# VDMEDA_Display1.net
KiCad netlist of a schematic drawn in Altium Designer
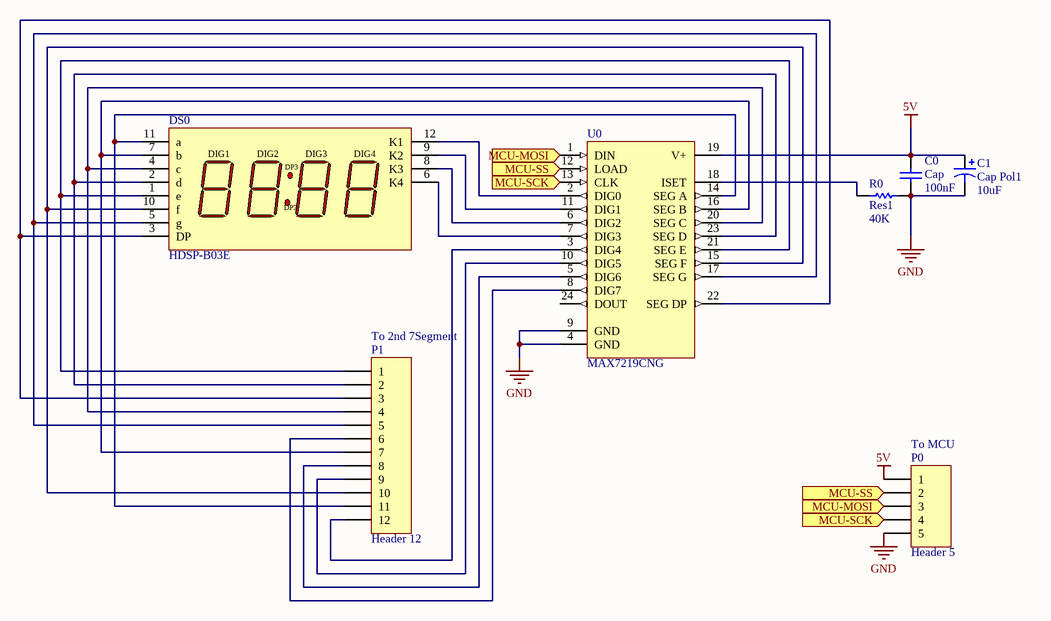
[diagram p0: VDMEDA_Display1.SchDoc]

(export (version "E")
  (design (tool "Eeschema 10.0.6"))
  (components
    (comp (ref "C0")
      (value "Cap")
      (footprint "RAD-0.3")
      (description "Capacitor")
      (fields (field (name "ALTIUM_VALUE") "100nF") (field (name "PUBLISHER") "Altium Limited"))
      (libsource (lib "Miscellaneous Devices") (part "Cap"))
    )
    (comp (ref "C1")
      (value "Cap Pol1")
      (footprint "RB7.6-15")
      (description "Polarized Capacitor (Radial)")
      (fields (field (name "ALTIUM_VALUE") "10uF") (field (name "PUBLISHER") "Altium Limited"))
      (libsource (lib "Miscellaneous Devices") (part "Cap Pol1"))
    )
    (comp (ref "DS0")
      (value "HDSP-B03E")
      (footprint "B-88")
      (description "14.22 mm GaP HER, Untinted, 88:88 4-Digit 7-Segment Display: CC, Gray Surface")
      (fields (field (name "PUBLISHER") "Altium Limited"))
      (libsource (lib "Agilent LED Display 7-Segment, 4-Digit") (part "HDSP-B03E"))
    )
    (comp (ref "P0")
      (value "Header 5")
      (footprint "HDR1X5")
      (description "Header, 5-Pin")
      (fields (field (name "PUBLISHER") "Altium Limited"))
      (libsource (lib "Miscellaneous Connectors") (part "Header 5"))
    )
    (comp (ref "P1")
      (value "Header 12")
      (footprint "HDR1X12")
      (description "Header, 12-Pin")
      (fields (field (name "PUBLISHER") "Altium Limited"))
      (libsource (lib "Miscellaneous Connectors") (part "Header 12"))
    )
    (comp (ref "R0")
      (value "Res1")
      (footprint "AXIAL-0.3")
      (description "Resistor")
      (fields (field (name "ALTIUM_VALUE") "40K") (field (name "PUBLISHER") "Altium Limited"))
      (libsource (lib "Miscellaneous Devices") (part "Res1"))
    )
    (comp (ref "U0")
      (value "MAX7219CNG")
      (footprint "NG24A")
      (description "Serially Interfaced, 8-Digit LED Display Driver")
      (fields (field (name "PUBLISHER") "Altium Limited"))
      (libsource (lib "Maxim Interface Display Driver") (part "MAX7219CNG"))
    )
  )
  (nets
    (net (code "1") (name "/MCU-MOSI") (class "Default")
      (node (ref "P0") (pin "3") (pinfunction "3_3") (pintype "passive"))
      (node (ref "U0") (pin "1") (pinfunction "DIN_1") (pintype "input"))
    )
    (net (code "2") (name "/MCU-SCK") (class "Default")
      (node (ref "P0") (pin "4") (pinfunction "4_4") (pintype "passive"))
      (node (ref "U0") (pin "13") (pinfunction "CLK_13") (pintype "input"))
    )
    (net (code "3") (name "/MCU-SS") (class "Default")
      (node (ref "P0") (pin "2") (pinfunction "2_2") (pintype "passive"))
      (node (ref "U0") (pin "12") (pinfunction "LOAD_12") (pintype "input"))
    )
    (net (code "4") (name "5V") (class "Default")
      (node (ref "C0") (pin "2") (pinfunction "2_2") (pintype "passive"))
      (node (ref "C1") (pin "1") (pinfunction "1_1") (pintype "passive"))
      (node (ref "P0") (pin "1") (pinfunction "1_1") (pintype "passive"))
      (node (ref "U0") (pin "19") (pinfunction "V+_19") (pintype "power_in"))
    )
    (net (code "5") (name "GND") (class "Default")
      (node (ref "C0") (pin "1") (pinfunction "1_1") (pintype "passive"))
      (node (ref "C1") (pin "2") (pinfunction "2_2") (pintype "passive"))
      (node (ref "P0") (pin "5") (pinfunction "5_5") (pintype "passive"))
      (node (ref "R0") (pin "2") (pinfunction "2_2") (pintype "passive"))
      (node (ref "U0") (pin "4") (pinfunction "GND_4") (pintype "power_in"))
      (node (ref "U0") (pin "9") (pinfunction "GND_9") (pintype "power_in"))
    )
    (net (code "6") (name "Net-(DS0-DP)") (class "Default")
      (node (ref "DS0") (pin "3") (pinfunction "DP_3") (pintype "passive"))
      (node (ref "P1") (pin "3") (pinfunction "3_3") (pintype "passive"))
      (node (ref "U0") (pin "22") (pinfunction "SEG_DP_22") (pintype "output"))
    )
    (net (code "7") (name "Net-(DS0-K1)") (class "Default")
      (node (ref "DS0") (pin "12") (pinfunction "K1_12") (pintype "passive"))
      (node (ref "U0") (pin "2") (pinfunction "DIG0_2") (pintype "output"))
    )
    (net (code "8") (name "Net-(DS0-K2)") (class "Default")
      (node (ref "DS0") (pin "9") (pinfunction "K2_9") (pintype "passive"))
      (node (ref "U0") (pin "11") (pinfunction "DIG1_11") (pintype "output"))
    )
    (net (code "9") (name "Net-(DS0-K3)") (class "Default")
      (node (ref "DS0") (pin "8") (pinfunction "K3_8") (pintype "passive"))
      (node (ref "U0") (pin "6") (pinfunction "DIG2_6") (pintype "output"))
    )
    (net (code "10") (name "Net-(DS0-K4)") (class "Default")
      (node (ref "DS0") (pin "6") (pinfunction "K4_6") (pintype "passive"))
      (node (ref "U0") (pin "7") (pinfunction "DIG3_7") (pintype "output"))
    )
    (net (code "11") (name "Net-(DS0-a)") (class "Default")
      (node (ref "DS0") (pin "11") (pinfunction "a_11") (pintype "passive"))
      (node (ref "P1") (pin "11") (pinfunction "11_11") (pintype "passive"))
      (node (ref "U0") (pin "14") (pinfunction "SEG_A_14") (pintype "output"))
    )
    (net (code "12") (name "Net-(DS0-b)") (class "Default")
      (node (ref "DS0") (pin "7") (pinfunction "b_7") (pintype "passive"))
      (node (ref "P1") (pin "7") (pinfunction "7_7") (pintype "passive"))
      (node (ref "U0") (pin "16") (pinfunction "SEG_B_16") (pintype "output"))
    )
    (net (code "13") (name "Net-(DS0-c)") (class "Default")
      (node (ref "DS0") (pin "4") (pinfunction "c_4") (pintype "passive"))
      (node (ref "P1") (pin "4") (pinfunction "4_4") (pintype "passive"))
      (node (ref "U0") (pin "20") (pinfunction "SEG_C_20") (pintype "output"))
    )
    (net (code "14") (name "Net-(DS0-d)") (class "Default")
      (node (ref "DS0") (pin "2") (pinfunction "d_2") (pintype "passive"))
      (node (ref "P1") (pin "2") (pinfunction "2_2") (pintype "passive"))
      (node (ref "U0") (pin "23") (pinfunction "SEG_D_23") (pintype "output"))
    )
    (net (code "15") (name "Net-(DS0-e)") (class "Default")
      (node (ref "DS0") (pin "1") (pinfunction "e_1") (pintype "passive"))
      (node (ref "P1") (pin "1") (pinfunction "1_1") (pintype "passive"))
      (node (ref "U0") (pin "21") (pinfunction "SEG_E_21") (pintype "output"))
    )
    (net (code "16") (name "Net-(DS0-f)") (class "Default")
      (node (ref "DS0") (pin "10") (pinfunction "f_10") (pintype "passive"))
      (node (ref "P1") (pin "10") (pinfunction "10_10") (pintype "passive"))
      (node (ref "U0") (pin "15") (pinfunction "SEG_F_15") (pintype "output"))
    )
    (net (code "17") (name "Net-(DS0-g)") (class "Default")
      (node (ref "DS0") (pin "5") (pinfunction "g_5") (pintype "passive"))
      (node (ref "P1") (pin "5") (pinfunction "5_5") (pintype "passive"))
      (node (ref "U0") (pin "17") (pinfunction "SEG_G_17") (pintype "output"))
    )
    (net (code "18") (name "Net-(U0-DIG4)") (class "Default")
      (node (ref "P1") (pin "12") (pinfunction "12_12") (pintype "passive"))
      (node (ref "U0") (pin "3") (pinfunction "DIG4_3") (pintype "output"))
    )
    (net (code "19") (name "Net-(U0-DIG5)") (class "Default")
      (node (ref "P1") (pin "9") (pinfunction "9_9") (pintype "passive"))
      (node (ref "U0") (pin "10") (pinfunction "DIG5_10") (pintype "output"))
    )
    (net (code "20") (name "Net-(U0-DIG6)") (class "Default")
      (node (ref "P1") (pin "8") (pinfunction "8_8") (pintype "passive"))
      (node (ref "U0") (pin "5") (pinfunction "DIG6_5") (pintype "output"))
    )
    (net (code "21") (name "Net-(U0-DIG7)") (class "Default")
      (node (ref "P1") (pin "6") (pinfunction "6_6") (pintype "passive"))
      (node (ref "U0") (pin "8") (pinfunction "DIG7_8") (pintype "output"))
    )
    (net (code "22") (name "Net-(U0-ISET)") (class "Default")
      (node (ref "R0") (pin "1") (pinfunction "1_1") (pintype "passive"))
      (node (ref "U0") (pin "18") (pinfunction "ISET_18") (pintype "passive"))
    )
    (net (code "23") (name "unconnected-(U0-DOUT-Pad24)") (class "Default")
      (node (ref "U0") (pin "24") (pinfunction "DOUT_24") (pintype "output"))
    )
  )
)
